# Sheet1.net
KiCad netlist of a schematic drawn in Altium Designer
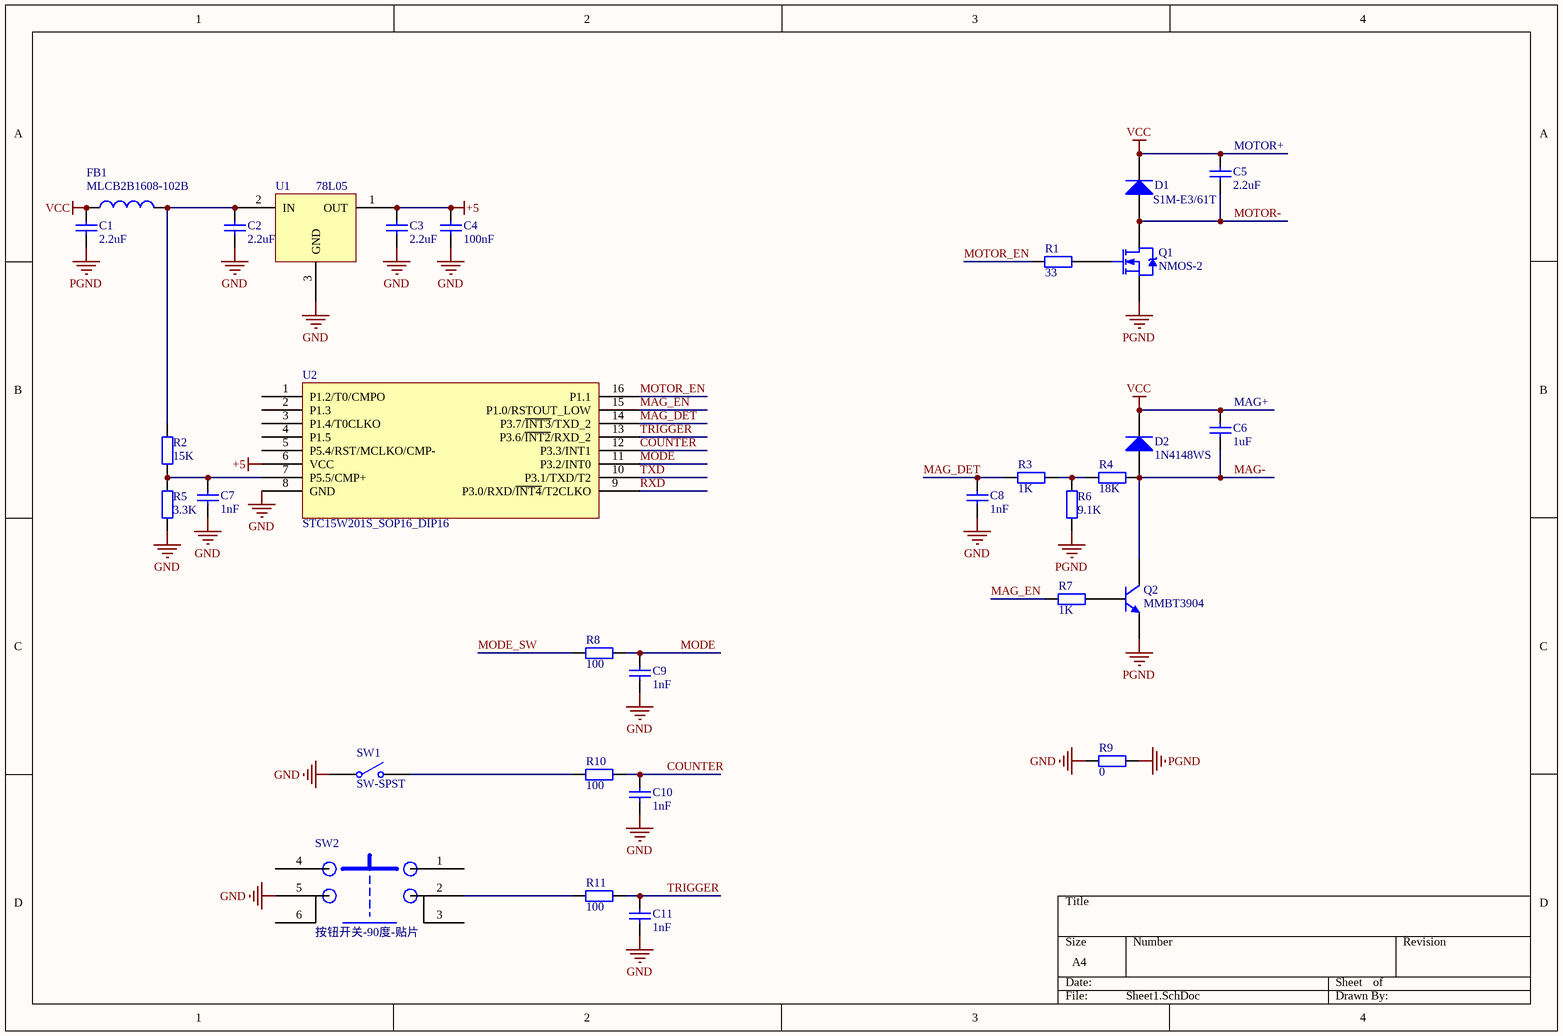
[diagram p0: Sheet1.SchDoc]

(export (version "E")
  (design (tool "Eeschema 10.0.6"))
  (components
    (comp (ref "C1")
      (value "2.2uF")
      (footprint "0805[cap]")
      (description "Chip Capacitor")
      (fields (field (name "Comment") "CT41L-0805-2C1-25V-225K"))
      (libsource (lib "passive") (part "Capacitor"))
    )
    (comp (ref "C2")
      (value "2.2uF")
      (footprint "0805[cap]")
      (description "Chip Capacitor")
      (fields (field (name "Comment") "CT41L-0805-2C1-25V-225K"))
      (libsource (lib "passive") (part "Capacitor"))
    )
    (comp (ref "C3")
      (value "2.2uF")
      (footprint "0805[cap]")
      (description "Chip Capacitor")
      (fields (field (name "Comment") "CT41L-0805-2C1-25V-225K"))
      (libsource (lib "passive") (part "Capacitor"))
    )
    (comp (ref "C4")
      (value "100nF")
      (footprint "0603[cap]")
      (description "Chip Capacitor")
      (fields (field (name "Comment") "CT41L-0603-2C1-50V-224K"))
      (libsource (lib "passive") (part "Capacitor"))
    )
    (comp (ref "C5")
      (value "2.2uF")
      (footprint "0805[cap]")
      (description "Chip Capacitor")
      (fields (field (name "Comment") "CT41L-0805-2C1-25V-225K"))
      (libsource (lib "passive") (part "Capacitor"))
    )
    (comp (ref "C6")
      (value "1uF")
      (footprint "0603[cap]")
      (description "Chip Capacitor")
      (fields (field (name "Comment") "CT41L-0603-2C1-50V-224K"))
      (libsource (lib "passive") (part "Capacitor"))
    )
    (comp (ref "C7")
      (value "1nF")
      (footprint "0603[cap]")
      (description "Chip Capacitor")
      (fields (field (name "Comment") "CT41L-0603-2C1-50V-224K"))
      (libsource (lib "passive") (part "Capacitor"))
    )
    (comp (ref "C8")
      (value "1nF")
      (footprint "0603[cap]")
      (description "Chip Capacitor")
      (fields (field (name "Comment") "CT41L-0603-2C1-50V-224K"))
      (libsource (lib "passive") (part "Capacitor"))
    )
    (comp (ref "C9")
      (value "1nF")
      (footprint "0603[cap]")
      (description "Chip Capacitor")
      (fields (field (name "Comment") "CT41L-0603-2C1-50V-224K"))
      (libsource (lib "passive") (part "Capacitor"))
    )
    (comp (ref "C10")
      (value "1nF")
      (footprint "0603[cap]")
      (description "Chip Capacitor")
      (fields (field (name "Comment") "CT41L-0603-2C1-50V-224K"))
      (libsource (lib "passive") (part "Capacitor"))
    )
    (comp (ref "C11")
      (value "1nF")
      (footprint "0603[cap]")
      (description "Chip Capacitor")
      (fields (field (name "Comment") "CT41L-0603-2C1-50V-224K"))
      (libsource (lib "passive") (part "Capacitor"))
    )
    (comp (ref "D1")
      (value "S1M-E3/61T")
      (footprint "M7")
      (description "1 Amp General Purpose Rectifier")
      (libsource (lib "Miscellaneous Devices") (part "Diode 1N4007"))
    )
    (comp (ref "D2")
      (value "1N4148WS")
      (footprint "SOD323")
      (description "Default Diode")
      (libsource (lib "Miscellaneous Devices") (part "Diode"))
    )
    (comp (ref "FB1")
      (value "MLCB2B1608-102B")
      (footprint "0603[bead]")
      (description "Chip Bead")
      (libsource (lib "passive") (part "bead"))
    )
    (comp (ref "Q1")
      (value "NMOS-2")
      (footprint "DPAK228P991X239-3N")
      (description "N-Channel Power MOSFET")
      (fields (field (name "PUBLISHER") "Altium Limited"))
      (libsource (lib "Miscellaneous Devices") (part "NMOS-2"))
    )
    (comp (ref "Q2")
      (value "MMBT3904")
      (footprint "SOT23-3N")
      (description "NPN General Purpose Amplifier")
      (libsource (lib "transistor") (part "MMBT3904"))
    )
    (comp (ref "R1")
      (value "33")
      (footprint "0603[res]")
      (description "Resistor")
      (fields (field (name "Comment") "RMK1608MB102J"))
      (libsource (lib "passive") (part "Resistor"))
    )
    (comp (ref "R2")
      (value "15K")
      (footprint "0603[res]")
      (description "Resistor")
      (fields (field (name "Comment") "RMK1608MB102J"))
      (libsource (lib "") (part "Resistor_1"))
    )
    (comp (ref "R3")
      (value "1K")
      (footprint "0603[res]")
      (description "Resistor")
      (fields (field (name "Comment") "RMK1608MB102J"))
      (libsource (lib "passive") (part "Resistor"))
    )
    (comp (ref "R4")
      (value "18K")
      (footprint "0603[res]")
      (description "Resistor")
      (fields (field (name "Comment") "RMK1608MB102J"))
      (libsource (lib "") (part "Resistor_2"))
    )
    (comp (ref "R5")
      (value "3.3K")
      (footprint "0603[res]")
      (description "Resistor")
      (fields (field (name "Comment") "RMK1608MB102J"))
      (libsource (lib "") (part "Resistor_1"))
    )
    (comp (ref "R6")
      (value "9.1K")
      (footprint "0603[res]")
      (description "Resistor")
      (fields (field (name "Comment") "RMK1608MB102J"))
      (libsource (lib "") (part "Resistor_1"))
    )
    (comp (ref "R7")
      (value "1K")
      (footprint "0603[res]")
      (description "Resistor")
      (fields (field (name "Comment") "RMK1608MB102J"))
      (libsource (lib "passive") (part "Resistor"))
    )
    (comp (ref "R8")
      (value "100")
      (footprint "0603[res]")
      (description "Resistor")
      (fields (field (name "Comment") "RMK1608MB102J"))
      (libsource (lib "passive") (part "Resistor"))
    )
    (comp (ref "R9")
      (value "0")
      (footprint "0603[res]")
      (description "Resistor")
      (fields (field (name "Comment") "RMK1608MB102J"))
      (libsource (lib "passive") (part "Resistor"))
    )
    (comp (ref "R10")
      (value "100")
      (footprint "0603[res]")
      (description "Resistor")
      (fields (field (name "Comment") "RMK1608MB102J"))
      (libsource (lib "passive") (part "Resistor"))
    )
    (comp (ref "R11")
      (value "100")
      (footprint "0603[res]")
      (description "Resistor")
      (fields (field (name "Comment") "RMK1608MB102J"))
      (libsource (lib "passive") (part "Resistor"))
    )
    (comp (ref "SW1")
      (value "SW-SPST")
      (footprint "JJJHRGG200NOPMRTR")
      (description "Single-Pole, Single-Throw Switch")
      (fields (field (name "PUBLISHER") "Altium Limited"))
      (libsource (lib "Miscellaneous Devices") (part "SW-SPST"))
    )
    (comp (ref "SW2")
      (value "按钮开关-90度-贴片")
      (footprint "按钮开关-90度-贴片")
      (libsource (lib "switch") (part "按钮开关-90度-贴片"))
    )
    (comp (ref "U1") (value "78L05") (footprint "SOT23-3N") (libsource (lib "power") (part "78L05")))
    (comp (ref "U2")
      (value "STC15W201S_SOP16_DIP16")
      (footprint "SOP16")
      (libsource (lib "stcmcu_altium_lib") (part "STC15W201S_SOP16_DIP16"))
    )
  )
  (nets
    (net (code "1") (name "+5") (class "Default")
      (node (ref "C3") (pin "1") (pinfunction "1_1") (pintype "passive"))
      (node (ref "C4") (pin "1") (pinfunction "1_1") (pintype "passive"))
      (node (ref "U1") (pin "1") (pinfunction "OUT_1") (pintype "passive"))
      (node (ref "U2") (pin "6") (pinfunction "VCC_6") (pintype "passive"))
    )
    (net (code "2") (name "/COUNTER") (class "Default")
      (node (ref "C10") (pin "1") (pinfunction "1_1") (pintype "passive"))
      (node (ref "R10") (pin "2") (pinfunction "2_2") (pintype "passive"))
      (node (ref "U2") (pin "12") (pinfunction "P3.3/INT1_12") (pintype "passive"))
    )
    (net (code "3") (name "/MAG-") (class "Default")
      (node (ref "C6") (pin "2") (pinfunction "2_2") (pintype "passive"))
      (node (ref "D2") (pin "1") (pinfunction "A_1") (pintype "passive"))
      (node (ref "Q2") (pin "3") (pinfunction "C_3") (pintype "passive"))
      (node (ref "R4") (pin "1") (pinfunction "1_1") (pintype "passive"))
    )
    (net (code "4") (name "/MAG_DET") (class "Default")
      (node (ref "C8") (pin "1") (pinfunction "1_1") (pintype "passive"))
      (node (ref "R3") (pin "1") (pinfunction "1_1") (pintype "passive"))
      (node (ref "U2") (pin "14") (pinfunction "P3.7/~{INT3}/TXD_2_14") (pintype "passive"))
    )
    (net (code "5") (name "/MAG_EN") (class "Default")
      (node (ref "R7") (pin "1") (pinfunction "1_1") (pintype "passive"))
      (node (ref "U2") (pin "15") (pinfunction "P1.0/RSTOUT_LOW_15") (pintype "passive"))
    )
    (net (code "6") (name "/MODE") (class "Default")
      (node (ref "C9") (pin "1") (pinfunction "1_1") (pintype "passive"))
      (node (ref "R8") (pin "2") (pinfunction "2_2") (pintype "passive"))
      (node (ref "U2") (pin "11") (pinfunction "P3.2/INT0_11") (pintype "passive"))
    )
    (net (code "7") (name "/MODE_SW") (class "Default")
      (node (ref "R8") (pin "1") (pinfunction "1_1") (pintype "passive"))
    )
    (net (code "8") (name "/MOTOR-") (class "Default")
      (node (ref "C5") (pin "1") (pinfunction "1_1") (pintype "passive"))
      (node (ref "D1") (pin "1") (pinfunction "A_1") (pintype "passive"))
      (node (ref "Q1") (pin "2") (pinfunction "D_2") (pintype "passive"))
    )
    (net (code "9") (name "/MOTOR_EN") (class "Default")
      (node (ref "R1") (pin "1") (pinfunction "1_1") (pintype "passive"))
      (node (ref "U2") (pin "16") (pinfunction "P1.1_16") (pintype "passive"))
    )
    (net (code "10") (name "/RXD") (class "Default")
      (node (ref "U2") (pin "9") (pinfunction "P3.0/RXD/~{INT4}/T2CLKO_9") (pintype "passive"))
    )
    (net (code "11") (name "/TRIGGER") (class "Default")
      (node (ref "C11") (pin "1") (pinfunction "1_1") (pintype "passive"))
      (node (ref "R11") (pin "2") (pinfunction "2_2") (pintype "passive"))
      (node (ref "U2") (pin "13") (pinfunction "P3.6/~{INT2}/RXD_2_13") (pintype "passive"))
    )
    (net (code "12") (name "/TXD") (class "Default")
      (node (ref "U2") (pin "10") (pinfunction "P3.1/TXD/T2_10") (pintype "passive"))
    )
    (net (code "13") (name "GND") (class "Default")
      (node (ref "C10") (pin "2") (pinfunction "2_2") (pintype "passive"))
      (node (ref "C11") (pin "2") (pinfunction "2_2") (pintype "passive"))
      (node (ref "C2") (pin "2") (pinfunction "2_2") (pintype "passive"))
      (node (ref "C3") (pin "2") (pinfunction "2_2") (pintype "passive"))
      (node (ref "C4") (pin "2") (pinfunction "2_2") (pintype "passive"))
      (node (ref "C7") (pin "2") (pinfunction "2_2") (pintype "passive"))
      (node (ref "C8") (pin "2") (pinfunction "2_2") (pintype "passive"))
      (node (ref "C9") (pin "2") (pinfunction "2_2") (pintype "passive"))
      (node (ref "R5") (pin "1") (pinfunction "1_1") (pintype "passive"))
      (node (ref "R9") (pin "1") (pinfunction "1_1") (pintype "passive"))
      (node (ref "SW1") (pin "1") (pinfunction "COMMON_1") (pintype "passive"))
      (node (ref "SW2") (pin "5") (pinfunction "5_5") (pintype "passive"))
      (node (ref "U1") (pin "3") (pinfunction "GND_3") (pintype "passive"))
      (node (ref "U2") (pin "8") (pinfunction "GND_8") (pintype "passive"))
    )
    (net (code "14") (name "Net-(Q1-G)") (class "Default")
      (node (ref "Q1") (pin "1") (pinfunction "G_1") (pintype "passive"))
      (node (ref "R1") (pin "2") (pinfunction "2_2") (pintype "passive"))
    )
    (net (code "15") (name "Net-(Q2-B)") (class "Default")
      (node (ref "Q2") (pin "1") (pinfunction "B_1") (pintype "passive"))
      (node (ref "R7") (pin "2") (pinfunction "2_2") (pintype "passive"))
    )
    (net (code "16") (name "Net-(R3-Pad2)") (class "Default")
      (node (ref "R3") (pin "2") (pinfunction "2_2") (pintype "passive"))
      (node (ref "R4") (pin "2") (pinfunction "2_2") (pintype "passive"))
      (node (ref "R6") (pin "2") (pinfunction "2_2") (pintype "passive"))
    )
    (net (code "17") (name "Net-(R11-Pad1)") (class "Default")
      (node (ref "R11") (pin "1") (pinfunction "1_1") (pintype "passive"))
      (node (ref "SW2") (pin "2") (pintype "passive"))
    )
    (net (code "18") (name "Net-(SW1-NO)") (class "Default")
      (node (ref "R10") (pin "1") (pinfunction "1_1") (pintype "passive"))
      (node (ref "SW1") (pin "2") (pinfunction "NO_2") (pintype "passive"))
    )
    (net (code "19") (name "Net-(U1-IN)") (class "Default")
      (node (ref "C2") (pin "1") (pinfunction "1_1") (pintype "passive"))
      (node (ref "FB1") (pin "2") (pinfunction "2_2") (pintype "passive"))
      (node (ref "R2") (pin "2") (pinfunction "2_2") (pintype "passive"))
      (node (ref "U1") (pin "2") (pinfunction "IN_2") (pintype "passive"))
    )
    (net (code "20") (name "Net-(U2-P5.5{slash}CMP+)") (class "Default")
      (node (ref "C7") (pin "1") (pinfunction "1_1") (pintype "passive"))
      (node (ref "R2") (pin "1") (pinfunction "1_1") (pintype "passive"))
      (node (ref "R5") (pin "2") (pinfunction "2_2") (pintype "passive"))
      (node (ref "U2") (pin "7") (pinfunction "P5.5/CMP+_7") (pintype "passive"))
    )
    (net (code "21") (name "PGND") (class "Default")
      (node (ref "C1") (pin "2") (pinfunction "2_2") (pintype "passive"))
      (node (ref "Q1") (pin "3") (pinfunction "S_3") (pintype "passive"))
      (node (ref "Q2") (pin "2") (pinfunction "E_2") (pintype "passive"))
      (node (ref "R6") (pin "1") (pinfunction "1_1") (pintype "passive"))
      (node (ref "R9") (pin "2") (pinfunction "2_2") (pintype "passive"))
    )
    (net (code "22") (name "VCC") (class "Default")
      (node (ref "C1") (pin "1") (pinfunction "1_1") (pintype "passive"))
      (node (ref "C5") (pin "2") (pinfunction "2_2") (pintype "passive"))
      (node (ref "C6") (pin "1") (pinfunction "1_1") (pintype "passive"))
      (node (ref "D1") (pin "2") (pinfunction "K_2") (pintype "passive"))
      (node (ref "D2") (pin "2") (pinfunction "K_2") (pintype "passive"))
      (node (ref "FB1") (pin "1") (pinfunction "1_1") (pintype "passive"))
    )
    (net (code "23") (name "unconnected-(SW2-Pad1)") (class "Default")
      (node (ref "SW2") (pin "1") (pintype "passive"))
    )
    (net (code "24") (name "unconnected-(SW2-Pad3)") (class "Default")
      (node (ref "SW2") (pin "3") (pintype "passive"))
    )
    (net (code "25") (name "unconnected-(SW2-Pad4)") (class "Default")
      (node (ref "SW2") (pin "4") (pinfunction "4_4") (pintype "passive"))
    )
    (net (code "26") (name "unconnected-(SW2-Pad6)") (class "Default")
      (node (ref "SW2") (pin "6") (pinfunction "6_6") (pintype "passive"))
    )
    (net (code "27") (name "unconnected-(U2-P1.2{slash}T0{slash}CMPO-Pad1)") (class "Default")
      (node (ref "U2") (pin "1") (pinfunction "P1.2/T0/CMPO_1") (pintype "passive"))
    )
    (net (code "28") (name "unconnected-(U2-P1.3-Pad2)") (class "Default")
      (node (ref "U2") (pin "2") (pinfunction "P1.3_2") (pintype "passive"))
    )
    (net (code "29") (name "unconnected-(U2-P1.4{slash}T0CLKO-Pad3)") (class "Default")
      (node (ref "U2") (pin "3") (pinfunction "P1.4/T0CLKO_3") (pintype "passive"))
    )
    (net (code "30") (name "unconnected-(U2-P1.5-Pad4)") (class "Default")
      (node (ref "U2") (pin "4") (pinfunction "P1.5_4") (pintype "passive"))
    )
    (net (code "31") (name "unconnected-(U2-P5.4{slash}RST{slash}MCLKO{slash}CMP--Pad5)") (class "Default")
      (node (ref "U2") (pin "5") (pinfunction "P5.4/RST/MCLKO/CMP-_5") (pintype "passive"))
    )
  )
)
